# ROM.net
KiCad netlist of a schematic drawn in Altium Designer
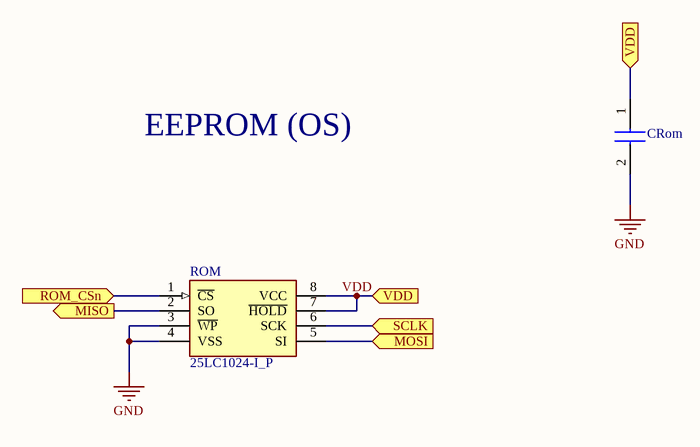
[diagram p0: ROM.SchDoc]

(export (version "E")
  (design (tool "Eeschema 10.0.6"))
  (components
    (comp (ref "CRom")
      (value "GRM155R71C104JA88D")
      (footprint "SamacSys:CAPC1005X55N")
      (description "Capacitor")
      (fields (field (name "MOUSER PART NUMBER") "81-GRM155R71C104JA8D"))
      (libsource (lib "*") (part "GRM155R71C104JA88D"))
    )
    (comp (ref "ROM")
      (value "25LC1024-I_P")
      (footprint "SamacSys:DIP781W56P254L950H533Q8N")
      (description "Integrated Circuit")
      (fields
        (field (name "MANUFACTURER_PART_NUMBER") "25LC1024-I/P")
        (field (name "MOUSER PART NUMBER") "579-25LC1024-I/P")
      )
      (libsource (lib "*") (part "25LC1024-I_P"))
    )
  )
  (nets
    (net (code "1") (name "/MISO") (class "Default")
      (node (ref "ROM") (pin "2") (pinfunction "SO_2") (pintype "passive"))
    )
    (net (code "2") (name "/MOSI") (class "Default")
      (node (ref "ROM") (pin "5") (pinfunction "SI_5") (pintype "passive"))
    )
    (net (code "3") (name "/ROM_CSn") (class "Default")
      (node (ref "ROM") (pin "1") (pinfunction "~{CS}_1") (pintype "input"))
    )
    (net (code "4") (name "/SCLK") (class "Default")
      (node (ref "ROM") (pin "6") (pinfunction "SCK_6") (pintype "passive"))
    )
    (net (code "5") (name "/VDD") (class "Default")
      (node (ref "CRom") (pin "1") (pinfunction "1_1") (pintype "passive"))
      (node (ref "ROM") (pin "7") (pinfunction "~{HOLD}_7") (pintype "passive"))
      (node (ref "ROM") (pin "8") (pinfunction "VCC_8") (pintype "power_in"))
    )
    (net (code "6") (name "GND") (class "Default")
      (node (ref "CRom") (pin "2") (pinfunction "2_2") (pintype "passive"))
      (node (ref "ROM") (pin "3") (pinfunction "~{WP}_3") (pintype "passive"))
      (node (ref "ROM") (pin "4") (pinfunction "VSS_4") (pintype "power_in"))
    )
  )
)
